# Humidifier.net
KiCad netlist of a schematic drawn in Altium Designer
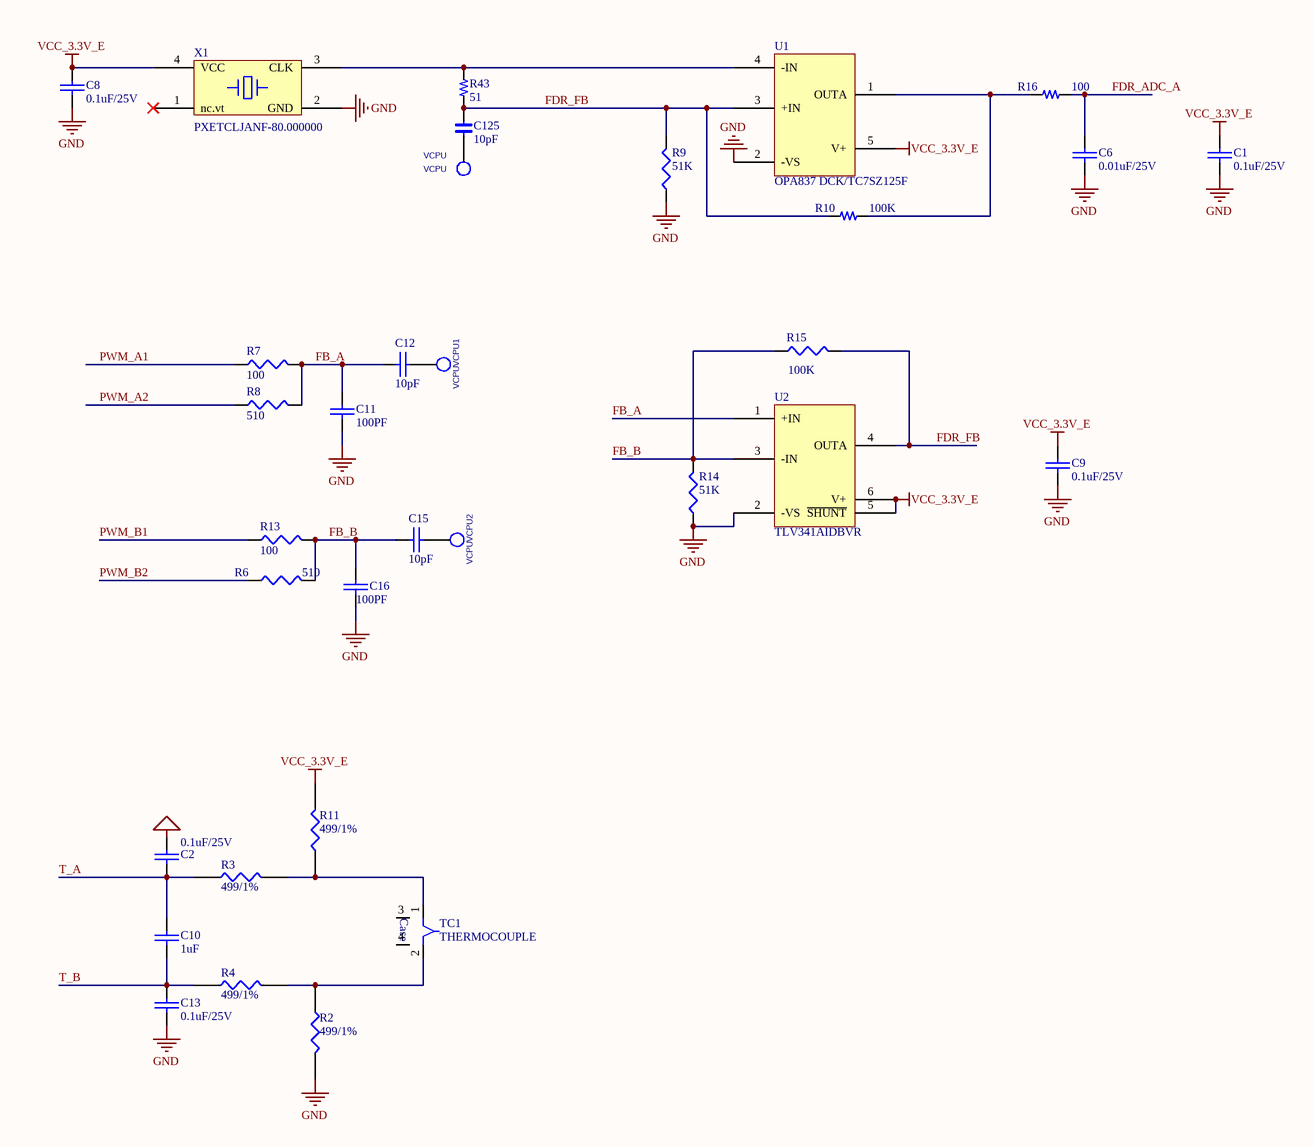
[diagram p0: Humidifier.SchDoc]

(export (version "E")
  (design (tool "Eeschema 10.0.6"))
  (components
    (comp (ref "C1")
      (value "0.1uF/25V")
      (footprint "0603C")
      (description "Capacitor")
      (libsource (lib "SM") (part "CAP"))
    )
    (comp (ref "C2")
      (value "0.1uF/25V")
      (footprint "0603c")
      (description "Capacitor")
      (libsource (lib "*") (part "CAP"))
    )
    (comp (ref "C6")
      (value "0.01uF/25V")
      (footprint "0603C")
      (description "Capacitor")
      (libsource (lib "SM") (part "CAP"))
    )
    (comp (ref "C8")
      (value "0.1uF/25V")
      (footprint "0603C")
      (description "Capacitor")
      (libsource (lib "SM") (part "CAP"))
    )
    (comp (ref "C9")
      (value "0.1uF/25V")
      (footprint "0603C")
      (description "Capacitor")
      (libsource (lib "SM") (part "CAP"))
    )
    (comp (ref "C10")
      (value "1uF")
      (footprint "0603c")
      (description "Capacitor")
      (libsource (lib "*") (part "CAP"))
    )
    (comp (ref "C11")
      (value "100PF")
      (footprint "0603C")
      (description "Capacitor")
      (libsource (lib "SM") (part "CAP"))
    )
    (comp (ref "C12")
      (value "10pF")
      (footprint "0603C")
      (description "Capacitor")
      (libsource (lib "SM") (part "CAP"))
    )
    (comp (ref "C13")
      (value "0.1uF/25V")
      (footprint "0603c")
      (description "Capacitor")
      (libsource (lib "*") (part "CAP"))
    )
    (comp (ref "C15")
      (value "10pF")
      (footprint "0603C")
      (description "Capacitor")
      (libsource (lib "SM") (part "CAP"))
    )
    (comp (ref "C16")
      (value "100PF")
      (footprint "0603C")
      (description "Capacitor")
      (libsource (lib "SM") (part "CAP"))
    )
    (comp (ref "C125")
      (value "10pF")
      (footprint "0603C")
      (description "C")
      (libsource (lib "YxmSCH") (part "C"))
    )
    (comp (ref "R2") (value "499/1%") (footprint "0603r") (libsource (lib "*") (part "RES1")))
    (comp (ref "R3") (value "499/1%") (footprint "0603r") (libsource (lib "*") (part "RES1")))
    (comp (ref "R4") (value "499/1%") (footprint "0603r") (libsource (lib "*") (part "RES1")))
    (comp (ref "R6")
      (value "510")
      (footprint "0603R")
      (description "Resistor")
      (fields (field (name "PUBLISHER") "Altium Limited"))
      (libsource (lib "SM") (part "Res3"))
    )
    (comp (ref "R7")
      (value "100")
      (footprint "0603R")
      (description "Resistor")
      (fields (field (name "PUBLISHER") "Altium Limited"))
      (libsource (lib "SM") (part "Res3"))
    )
    (comp (ref "R8")
      (value "510")
      (footprint "0603R")
      (description "Resistor")
      (fields (field (name "PUBLISHER") "Altium Limited"))
      (libsource (lib "SM") (part "Res3"))
    )
    (comp (ref "R9")
      (value "51K")
      (footprint "0603R")
      (description "Resistor")
      (fields (field (name "PUBLISHER") "Altium Limited"))
      (libsource (lib "SM") (part "Res3"))
    )
    (comp (ref "R10")
      (value "100K")
      (footprint "0603R")
      (description "R")
      (libsource (lib "JRJ_1") (part "R"))
    )
    (comp (ref "R11") (value "499/1%") (footprint "0603r") (libsource (lib "*") (part "RES1")))
    (comp (ref "R13")
      (value "100")
      (footprint "0603R")
      (description "Resistor")
      (fields (field (name "PUBLISHER") "Altium Limited"))
      (libsource (lib "SM") (part "Res3"))
    )
    (comp (ref "R14")
      (value "51K")
      (footprint "0603R")
      (description "Resistor")
      (fields (field (name "PUBLISHER") "Altium Limited"))
      (libsource (lib "SM") (part "Res3"))
    )
    (comp (ref "R15")
      (value "100K")
      (footprint "0603R")
      (description "Resistor")
      (fields (field (name "PUBLISHER") "Altium Limited"))
      (libsource (lib "SM") (part "Res3"))
    )
    (comp (ref "R16")
      (value "100")
      (footprint "0603R")
      (description "R")
      (libsource (lib "JRJ_1") (part "R"))
    )
    (comp (ref "R43") (value "51") (footprint "0603r") (description "R") (libsource (lib "JRJ") (part "R")))
    (comp (ref "TC1") (value "THERMOCOUPLE") (footprint "0603R") (libsource (lib "*") (part "THERMOCOUPLE")))
    (comp (ref "U1")
      (value "OPA837 DCK/TC7SZ125F")
      (footprint "SC70-5")
      (libsource (lib "Schlib_20110825") (part "OPA837 DCK"))
    )
    (comp (ref "U2")
      (value "TLV341AIDBVR")
      (footprint "SOT-23-6")
      (libsource (lib "Schlib_20110825") (part "TLV341AIDBVR"))
    )
    (comp (ref "VCPU") (value "VCPU") (footprint "probe") (libsource (lib "*") (part "T_POINT_R")))
    (comp (ref "VCPU1") (value "VCPU") (footprint "probe") (libsource (lib "*") (part "T_POINT_R")))
    (comp (ref "VCPU2") (value "VCPU") (footprint "probe") (libsource (lib "*") (part "T_POINT_R")))
    (comp (ref "X1")
      (value "PXETCLJANF-80.000000")
      (footprint "XTAL4TN_7050")
      (libsource (lib "Y0801_V13") (part "XTAL4S"))
    )
  )
  (nets
    (net (code "1") (name "/FB_A") (class "Default")
      (node (ref "C11") (pin "1") (pinfunction "1_1") (pintype "passive"))
      (node (ref "C12") (pin "2") (pinfunction "2_2") (pintype "passive"))
      (node (ref "R7") (pin "2") (pinfunction "2_2") (pintype "passive"))
      (node (ref "R8") (pin "2") (pinfunction "2_2") (pintype "passive"))
      (node (ref "U2") (pin "1") (pinfunction "+IN_1") (pintype "passive"))
    )
    (net (code "2") (name "/FB_B") (class "Default")
      (node (ref "C15") (pin "1") (pinfunction "1_1") (pintype "passive"))
      (node (ref "C16") (pin "1") (pinfunction "1_1") (pintype "passive"))
      (node (ref "R13") (pin "2") (pinfunction "2_2") (pintype "passive"))
      (node (ref "R14") (pin "2") (pinfunction "2_2") (pintype "passive"))
      (node (ref "R15") (pin "1") (pinfunction "1_1") (pintype "passive"))
      (node (ref "R6") (pin "2") (pinfunction "2_2") (pintype "passive"))
      (node (ref "U2") (pin "3") (pinfunction "-IN_3") (pintype "passive"))
    )
    (net (code "3") (name "/FDR_ADC_A") (class "Default")
      (node (ref "C6") (pin "2") (pinfunction "2_2") (pintype "passive"))
      (node (ref "R16") (pin "2") (pintype "passive"))
    )
    (net (code "4") (name "/FDR_FB") (class "Default")
      (node (ref "C125") (pin "1") (pintype "passive"))
      (node (ref "R10") (pin "1") (pintype "passive"))
      (node (ref "R15") (pin "2") (pinfunction "2_2") (pintype "passive"))
      (node (ref "R43") (pin "2") (pintype "passive"))
      (node (ref "R9") (pin "2") (pinfunction "2_2") (pintype "passive"))
      (node (ref "U1") (pin "3") (pinfunction "+IN_3") (pintype "passive"))
      (node (ref "U2") (pin "4") (pinfunction "OUTA_4") (pintype "passive"))
    )
    (net (code "5") (name "/PWM_A1") (class "Default")
      (node (ref "R7") (pin "1") (pinfunction "1_1") (pintype "passive"))
    )
    (net (code "6") (name "/PWM_A2") (class "Default")
      (node (ref "R8") (pin "1") (pinfunction "1_1") (pintype "passive"))
    )
    (net (code "7") (name "/PWM_B1") (class "Default")
      (node (ref "R13") (pin "1") (pinfunction "1_1") (pintype "passive"))
    )
    (net (code "8") (name "/PWM_B2") (class "Default")
      (node (ref "R6") (pin "1") (pinfunction "1_1") (pintype "passive"))
    )
    (net (code "9") (name "/T_A") (class "Default")
      (node (ref "C10") (pin "1") (pinfunction "1_1") (pintype "passive"))
      (node (ref "C2") (pin "1") (pinfunction "1_1") (pintype "passive"))
      (node (ref "R3") (pin "1") (pinfunction "1_1") (pintype "passive"))
    )
    (net (code "10") (name "/T_B") (class "Default")
      (node (ref "C10") (pin "2") (pinfunction "2_2") (pintype "passive"))
      (node (ref "C13") (pin "1") (pinfunction "1_1") (pintype "passive"))
      (node (ref "R4") (pin "1") (pinfunction "1_1") (pintype "passive"))
    )
    (net (code "11") (name "GND") (class "Default")
      (node (ref "C1") (pin "1") (pinfunction "1_1") (pintype "passive"))
      (node (ref "C11") (pin "2") (pinfunction "2_2") (pintype "passive"))
      (node (ref "C13") (pin "2") (pinfunction "2_2") (pintype "passive"))
      (node (ref "C16") (pin "2") (pinfunction "2_2") (pintype "passive"))
      (node (ref "C2") (pin "2") (pinfunction "2_2") (pintype "passive"))
      (node (ref "C6") (pin "1") (pinfunction "1_1") (pintype "passive"))
      (node (ref "C8") (pin "2") (pinfunction "2_2") (pintype "passive"))
      (node (ref "C9") (pin "1") (pinfunction "1_1") (pintype "passive"))
      (node (ref "R14") (pin "1") (pinfunction "1_1") (pintype "passive"))
      (node (ref "R2") (pin "2") (pinfunction "2_2") (pintype "passive"))
      (node (ref "R9") (pin "1") (pinfunction "1_1") (pintype "passive"))
      (node (ref "U1") (pin "2") (pinfunction "-VS_2") (pintype "passive"))
      (node (ref "U2") (pin "2") (pinfunction "-VS_2") (pintype "passive"))
      (node (ref "X1") (pin "2") (pinfunction "GND_2") (pintype "power_in"))
    )
    (net (code "12") (name "Net-(R2-Pad1)") (class "Default")
      (node (ref "R2") (pin "1") (pinfunction "1_1") (pintype "passive"))
      (node (ref "R4") (pin "2") (pinfunction "2_2") (pintype "passive"))
      (node (ref "TC1") (pin "2") (pinfunction "2_2") (pintype "passive"))
    )
    (net (code "13") (name "Net-(R11-Pad1)") (class "Default")
      (node (ref "R11") (pin "1") (pinfunction "1_1") (pintype "passive"))
      (node (ref "R3") (pin "2") (pinfunction "2_2") (pintype "passive"))
      (node (ref "TC1") (pin "1") (pinfunction "1_1") (pintype "passive"))
    )
    (net (code "14") (name "Net-(U1--IN)") (class "Default")
      (node (ref "R43") (pin "1") (pintype "passive"))
      (node (ref "U1") (pin "4") (pinfunction "-IN_4") (pintype "passive"))
      (node (ref "X1") (pin "3") (pinfunction "CLK_3") (pintype "passive"))
    )
    (net (code "15") (name "Net-(U1-OUTA)") (class "Default")
      (node (ref "R10") (pin "2") (pintype "passive"))
      (node (ref "R16") (pin "1") (pintype "passive"))
      (node (ref "U1") (pin "1") (pinfunction "OUTA_1") (pintype "passive"))
    )
    (net (code "16") (name "Net-(VCPU-TP)") (class "Default")
      (node (ref "C125") (pin "2") (pintype "passive"))
      (node (ref "VCPU") (pin "1") (pinfunction "TP_1") (pintype "passive"))
    )
    (net (code "17") (name "Net-(VCPU1-TP)") (class "Default")
      (node (ref "C12") (pin "1") (pinfunction "1_1") (pintype "passive"))
      (node (ref "VCPU1") (pin "1") (pinfunction "TP_1") (pintype "passive"))
    )
    (net (code "18") (name "Net-(VCPU2-TP)") (class "Default")
      (node (ref "C15") (pin "2") (pinfunction "2_2") (pintype "passive"))
      (node (ref "VCPU2") (pin "1") (pinfunction "TP_1") (pintype "passive"))
    )
    (net (code "19") (name "VCC_3.3V_E") (class "Default")
      (node (ref "C1") (pin "2") (pinfunction "2_2") (pintype "passive"))
      (node (ref "C8") (pin "1") (pinfunction "1_1") (pintype "passive"))
      (node (ref "C9") (pin "2") (pinfunction "2_2") (pintype "passive"))
      (node (ref "R11") (pin "2") (pinfunction "2_2") (pintype "passive"))
      (node (ref "U1") (pin "5") (pinfunction "V+_5") (pintype "passive"))
      (node (ref "U2") (pin "5") (pinfunction "~{SHUNT}_5") (pintype "passive"))
      (node (ref "U2") (pin "6") (pinfunction "V+_6") (pintype "passive"))
      (node (ref "X1") (pin "4") (pinfunction "VCC_4") (pintype "power_in"))
    )
    (net (code "20") (name "unconnected-(TC1-Pad3)") (class "Default")
      (node (ref "TC1") (pin "3") (pinfunction "3_3") (pintype "passive"))
    )
    (net (code "21") (name "unconnected-(TC1-Pad4)") (class "Default")
      (node (ref "TC1") (pin "4") (pinfunction "4_4") (pintype "passive"))
    )
    (net (code "22") (name "unconnected-(X1-nc.vt-Pad1)") (class "Default")
      (node (ref "X1") (pin "1") (pinfunction "nc.vt_1") (pintype "passive+no_connect"))
    )
  )
)
